# CHGslaBAT.net
KiCad netlist of a schematic drawn in EAGLE
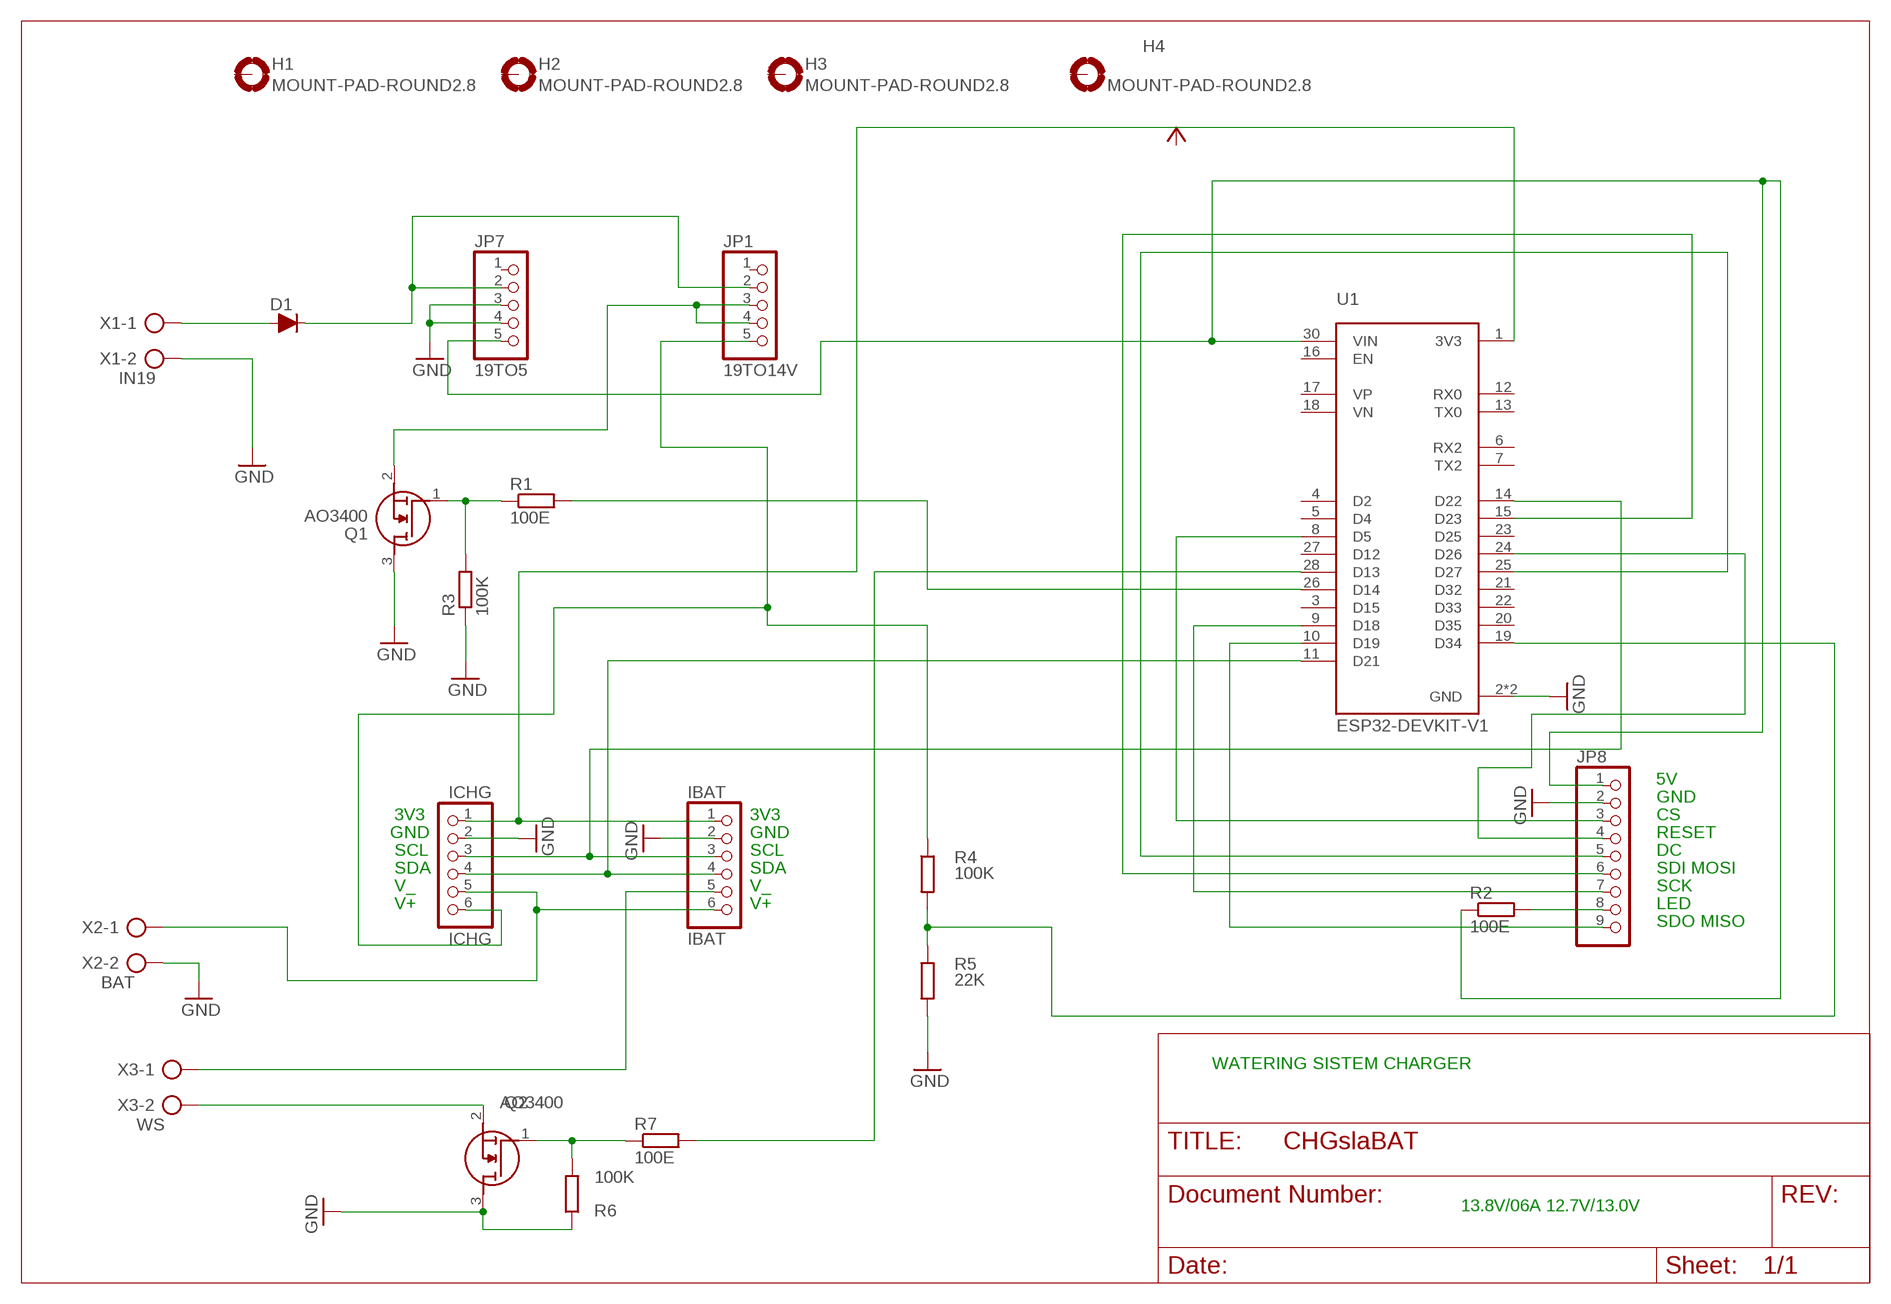
[diagram p0: schematic, sheet 1]

(export (version "E")
  (design (tool "Eeschema 10.0.6"))
  (components
    (comp (ref "D1")
      (value "D-FILL-SOD-80")
      (footprint "eagle-import:SOD80")
      (libsource (lib "eagle-import") (part "D-FILL-SOD-80"))
    )
    (comp (ref "H1")
      (value "MOUNT-PAD-ROUND2.8")
      (footprint "eagle-import:2,8-PAD")
      (libsource (lib "eagle-import") (part "MOUNT-PAD-ROUND2.8"))
    )
    (comp (ref "H2")
      (value "MOUNT-PAD-ROUND2.8")
      (footprint "eagle-import:2,8-PAD")
      (libsource (lib "eagle-import") (part "MOUNT-PAD-ROUND2.8"))
    )
    (comp (ref "H3")
      (value "MOUNT-PAD-ROUND2.8")
      (footprint "eagle-import:2,8-PAD")
      (libsource (lib "eagle-import") (part "MOUNT-PAD-ROUND2.8"))
    )
    (comp (ref "H4")
      (value "MOUNT-PAD-ROUND2.8")
      (footprint "eagle-import:2,8-PAD")
      (libsource (lib "eagle-import") (part "MOUNT-PAD-ROUND2.8"))
    )
    (comp (ref "IBAT")
      (value "IBAT")
      (footprint "eagle-import:1X06")
      (libsource (lib "eagle-import") (part "PINHD-1X6"))
    )
    (comp (ref "ICHG")
      (value "ICHG")
      (footprint "eagle-import:1X06")
      (libsource (lib "eagle-import") (part "PINHD-1X6"))
    )
    (comp (ref "JP1")
      (value "19TO14V")
      (footprint "eagle-import:1X05")
      (libsource (lib "eagle-import") (part "PINHD-1X5"))
    )
    (comp (ref "JP7")
      (value "19TO5")
      (footprint "eagle-import:1X05")
      (libsource (lib "eagle-import") (part "PINHD-1X5"))
    )
    (comp (ref "JP8")
      (value "PINHD-1X9")
      (footprint "eagle-import:1X09")
      (libsource (lib "eagle-import") (part "PINHD-1X9"))
    )
    (comp (ref "Q1")
      (value "AO3400")
      (footprint "eagle-import:SOT95P280X125-3N")
      (fields (field (name "MF") "Microdiode Electronics"))
      (libsource (lib "eagle-import") (part "AO3400"))
    )
    (comp (ref "Q2")
      (value "AO3400")
      (footprint "eagle-import:SOT95P280X125-3N")
      (description "Trans MOSFET N-CH 30V 5.7A 3-Pin SOT-23 T/R")
      (fields
        (field (name "MF") "Microdiode Electronics")
        (field (name "AVAILABILITY") "Not in stock")
        (field (name "CHECK_PRICES") "https://www.snapeda.com/parts/AO3400/Applied+Avionics/view-part/?ref=eda")
        (field (name "MF_1") "Microdiode Electronics")
        (field (name "MP") "AO3400")
        (field (name "PACKAGE") "None")
        (field (name "PRICE") "None")
        (field (name "SNAPEDA_LINK") "https://www.snapeda.com/parts/AO3400/Applied+Avionics/view-part/?ref=snap")
      )
      (libsource (lib "eagle-import") (part "AO3400"))
    )
    (comp (ref "R1")
      (value "100E")
      (footprint "eagle-import:M0805")
      (libsource (lib "eagle-import") (part "R-EU_M0805"))
    )
    (comp (ref "R2")
      (value "100E")
      (footprint "eagle-import:M0805")
      (libsource (lib "eagle-import") (part "R-EU_M0805"))
    )
    (comp (ref "R3")
      (value "100K")
      (footprint "eagle-import:M0805")
      (libsource (lib "eagle-import") (part "R-EU_M0805"))
    )
    (comp (ref "R4")
      (value "100K")
      (footprint "eagle-import:M0805")
      (libsource (lib "eagle-import") (part "R-EU_M0805"))
    )
    (comp (ref "R5")
      (value "22K")
      (footprint "eagle-import:M0805")
      (libsource (lib "eagle-import") (part "R-EU_M0805"))
    )
    (comp (ref "R6")
      (value "100K")
      (footprint "eagle-import:M0805")
      (libsource (lib "eagle-import") (part "R-EU_M0805"))
    )
    (comp (ref "R7")
      (value "100E")
      (footprint "eagle-import:M0805")
      (libsource (lib "eagle-import") (part "R-EU_M0805"))
    )
    (comp (ref "U1")
      (value "ESP32-DEVKIT-V1")
      (footprint "eagle-import:MODULE_ESP32_DEVKIT_V1")
      (fields (field (name "MF") "Do it"))
      (libsource (lib "eagle-import") (part "ESP32-DEVKIT-V1"))
    )
    (comp (ref "X1")
      (value "IN19")
      (footprint "eagle-import:AK300_2")
      (libsource (lib "eagle-import") (part "AK300/2"))
    )
    (comp (ref "X2")
      (value "BAT")
      (footprint "eagle-import:AK300_2")
      (libsource (lib "eagle-import") (part "AK300/2"))
    )
    (comp (ref "X3")
      (value "WS")
      (footprint "eagle-import:AK300_2")
      (libsource (lib "eagle-import") (part "AK300/2"))
    )
  )
  (nets
    (net (code "2") (name "GND") (class "Default")
      (node (ref "IBAT") (pin "2") (pinfunction "2_2") (pintype "passive"))
      (node (ref "ICHG") (pin "2") (pinfunction "2_2") (pintype "passive"))
      (node (ref "JP7") (pin "3") (pinfunction "3_3") (pintype "passive"))
      (node (ref "JP7") (pin "4") (pinfunction "4_4") (pintype "passive"))
      (node (ref "JP8") (pin "2") (pinfunction "2_2") (pintype "passive"))
      (node (ref "Q1") (pin "3") (pinfunction "D_3") (pintype "bidirectional"))
      (node (ref "Q2") (pin "3") (pinfunction "D_3") (pintype "bidirectional"))
      (node (ref "R3") (pin "1") (pinfunction "1_1") (pintype "passive"))
      (node (ref "R5") (pin "2") (pinfunction "2_2") (pintype "passive"))
      (node (ref "R6") (pin "1") (pinfunction "1_1") (pintype "passive"))
      (node (ref "U1") (pin "2") (pinfunction "GND_2") (pintype "power_in"))
      (node (ref "U1") (pin "29") (pinfunction "GND_29") (pintype "power_in"))
      (node (ref "X1") (pin "2") (pinfunction "KL_2") (pintype "passive"))
      (node (ref "X2") (pin "2") (pinfunction "KL_2") (pintype "passive"))
    )
    (net (code "3") (name "Net-(D1-A)") (class "Default")
      (node (ref "D1") (pin "2") (pinfunction "A_2") (pintype "passive"))
      (node (ref "X1") (pin "1") (pinfunction "KL_1") (pintype "passive"))
    )
    (net (code "4") (name "Net-(D1-C)") (class "Default")
      (node (ref "D1") (pin "1") (pinfunction "C_1") (pintype "passive"))
      (node (ref "JP1") (pin "2") (pinfunction "2_2") (pintype "passive"))
      (node (ref "JP7") (pin "2") (pinfunction "2_2") (pintype "passive"))
    )
    (net (code "5") (name "Net-(ICHG-Pad6)") (class "Default")
      (node (ref "ICHG") (pin "6") (pinfunction "6_6") (pintype "passive"))
      (node (ref "JP1") (pin "5") (pinfunction "5_5") (pintype "passive"))
      (node (ref "R4") (pin "1") (pinfunction "1_1") (pintype "passive"))
    )
    (net (code "6") (name "Net-(JP8-Pad8)") (class "Default")
      (node (ref "JP8") (pin "8") (pinfunction "8_8") (pintype "passive"))
      (node (ref "R2") (pin "2") (pinfunction "2_2") (pintype "passive"))
    )
    (net (code "7") (name "Net-(Q1-G)") (class "Default")
      (node (ref "Q1") (pin "1") (pinfunction "G_1") (pintype "bidirectional"))
      (node (ref "R1") (pin "1") (pinfunction "1_1") (pintype "passive"))
      (node (ref "R3") (pin "2") (pinfunction "2_2") (pintype "passive"))
    )
    (net (code "8") (name "Net-(Q1-S)") (class "Default")
      (node (ref "JP1") (pin "3") (pinfunction "3_3") (pintype "passive"))
      (node (ref "JP1") (pin "4") (pinfunction "4_4") (pintype "passive"))
      (node (ref "Q1") (pin "2") (pinfunction "S_2") (pintype "bidirectional"))
    )
    (net (code "9") (name "Net-(Q2-G)") (class "Default")
      (node (ref "Q2") (pin "1") (pinfunction "G_1") (pintype "bidirectional"))
      (node (ref "R6") (pin "2") (pinfunction "2_2") (pintype "passive"))
      (node (ref "R7") (pin "1") (pinfunction "1_1") (pintype "passive"))
    )
    (net (code "10") (name "Net-(Q2-S)") (class "Default")
      (node (ref "Q2") (pin "2") (pinfunction "S_2") (pintype "bidirectional"))
      (node (ref "X3") (pin "2") (pinfunction "KL_2") (pintype "passive"))
    )
    (net (code "11") (name "Net-(U1-3V3)") (class "Default")
      (node (ref "IBAT") (pin "1") (pinfunction "1_1") (pintype "passive"))
      (node (ref "ICHG") (pin "1") (pinfunction "1_1") (pintype "passive"))
      (node (ref "U1") (pin "1") (pinfunction "3V3_1") (pintype "output"))
    )
    (net (code "12") (name "Net-(U1-D5)") (class "Default")
      (node (ref "JP8") (pin "3") (pinfunction "3_3") (pintype "passive"))
      (node (ref "U1") (pin "8") (pinfunction "D5_8") (pintype "bidirectional"))
    )
    (net (code "13") (name "Net-(U1-D13)") (class "Default")
      (node (ref "R7") (pin "2") (pinfunction "2_2") (pintype "passive"))
      (node (ref "U1") (pin "28") (pinfunction "D13_28") (pintype "bidirectional"))
    )
    (net (code "14") (name "Net-(U1-D14)") (class "Default")
      (node (ref "R1") (pin "2") (pinfunction "2_2") (pintype "passive"))
      (node (ref "U1") (pin "26") (pinfunction "D14_26") (pintype "bidirectional"))
    )
    (net (code "15") (name "Net-(U1-D18)") (class "Default")
      (node (ref "JP8") (pin "7") (pinfunction "7_7") (pintype "passive"))
      (node (ref "U1") (pin "9") (pinfunction "D18_9") (pintype "bidirectional"))
    )
    (net (code "16") (name "Net-(U1-D19)") (class "Default")
      (node (ref "JP8") (pin "9") (pinfunction "9_9") (pintype "passive"))
      (node (ref "U1") (pin "10") (pinfunction "D19_10") (pintype "bidirectional"))
    )
    (net (code "17") (name "Net-(U1-D21)") (class "Default")
      (node (ref "IBAT") (pin "4") (pinfunction "4_4") (pintype "passive"))
      (node (ref "ICHG") (pin "4") (pinfunction "4_4") (pintype "passive"))
      (node (ref "U1") (pin "11") (pinfunction "D21_11") (pintype "bidirectional"))
    )
    (net (code "18") (name "Net-(U1-D22)") (class "Default")
      (node (ref "IBAT") (pin "3") (pinfunction "3_3") (pintype "passive"))
      (node (ref "ICHG") (pin "3") (pinfunction "3_3") (pintype "passive"))
      (node (ref "U1") (pin "14") (pinfunction "D22_14") (pintype "bidirectional"))
    )
    (net (code "19") (name "Net-(U1-D23)") (class "Default")
      (node (ref "JP8") (pin "6") (pinfunction "6_6") (pintype "passive"))
      (node (ref "U1") (pin "15") (pinfunction "D23_15") (pintype "bidirectional"))
    )
    (net (code "20") (name "Net-(U1-D26)") (class "Default")
      (node (ref "JP8") (pin "4") (pinfunction "4_4") (pintype "passive"))
      (node (ref "U1") (pin "24") (pinfunction "D26_24") (pintype "bidirectional"))
    )
    (net (code "21") (name "Net-(U1-D27)") (class "Default")
      (node (ref "JP8") (pin "5") (pinfunction "5_5") (pintype "passive"))
      (node (ref "U1") (pin "25") (pinfunction "D27_25") (pintype "bidirectional"))
    )
    (net (code "22") (name "Net-(U1-D34)") (class "Default")
      (node (ref "R4") (pin "2") (pinfunction "2_2") (pintype "passive"))
      (node (ref "R5") (pin "1") (pinfunction "1_1") (pintype "passive"))
      (node (ref "U1") (pin "19") (pinfunction "D34_19") (pintype "bidirectional"))
    )
    (net (code "23") (name "Net-(U1-VIN)") (class "Default")
      (node (ref "JP7") (pin "5") (pinfunction "5_5") (pintype "passive"))
      (node (ref "JP8") (pin "1") (pinfunction "1_1") (pintype "passive"))
      (node (ref "R2") (pin "1") (pinfunction "1_1") (pintype "passive"))
      (node (ref "U1") (pin "30") (pinfunction "VIN_30") (pintype "input"))
    )
    (net (code "24") (name "Net-(X2A-KL)") (class "Default")
      (node (ref "IBAT") (pin "6") (pinfunction "6_6") (pintype "passive"))
      (node (ref "ICHG") (pin "5") (pinfunction "5_5") (pintype "passive"))
      (node (ref "X2") (pin "1") (pinfunction "KL_1") (pintype "passive"))
    )
    (net (code "25") (name "Net-(X3A-KL)") (class "Default")
      (node (ref "IBAT") (pin "5") (pinfunction "5_5") (pintype "passive"))
      (node (ref "X3") (pin "1") (pinfunction "KL_1") (pintype "passive"))
    )
    (net (code "26") (name "unconnected-(H1-MOUNT-PadB2,8)") (class "Default")
      (node (ref "H1") (pin "B2,8") (pinfunction "MOUNT_B2,8") (pintype "passive"))
    )
    (net (code "27") (name "unconnected-(H2-MOUNT-PadB2,8)") (class "Default")
      (node (ref "H2") (pin "B2,8") (pinfunction "MOUNT_B2,8") (pintype "passive"))
    )
    (net (code "28") (name "unconnected-(H3-MOUNT-PadB2,8)") (class "Default")
      (node (ref "H3") (pin "B2,8") (pinfunction "MOUNT_B2,8") (pintype "passive"))
    )
    (net (code "29") (name "unconnected-(H4-MOUNT-PadB2,8)") (class "Default")
      (node (ref "H4") (pin "B2,8") (pinfunction "MOUNT_B2,8") (pintype "passive"))
    )
    (net (code "30") (name "unconnected-(JP1-Pad1)") (class "Default")
      (node (ref "JP1") (pin "1") (pinfunction "1_1") (pintype "passive"))
    )
    (net (code "31") (name "unconnected-(JP7-Pad1)") (class "Default")
      (node (ref "JP7") (pin "1") (pinfunction "1_1") (pintype "passive"))
    )
    (net (code "32") (name "unconnected-(U1-D2-Pad4)") (class "Default")
      (node (ref "U1") (pin "4") (pinfunction "D2_4") (pintype "bidirectional"))
    )
    (net (code "33") (name "unconnected-(U1-D4-Pad5)") (class "Default")
      (node (ref "U1") (pin "5") (pinfunction "D4_5") (pintype "bidirectional"))
    )
    (net (code "34") (name "unconnected-(U1-D12-Pad27)") (class "Default")
      (node (ref "U1") (pin "27") (pinfunction "D12_27") (pintype "bidirectional"))
    )
    (net (code "35") (name "unconnected-(U1-D15-Pad3)") (class "Default")
      (node (ref "U1") (pin "3") (pinfunction "D15_3") (pintype "bidirectional"))
    )
    (net (code "36") (name "unconnected-(U1-D25-Pad23)") (class "Default")
      (node (ref "U1") (pin "23") (pinfunction "D25_23") (pintype "bidirectional"))
    )
    (net (code "37") (name "unconnected-(U1-D32-Pad21)") (class "Default")
      (node (ref "U1") (pin "21") (pinfunction "D32_21") (pintype "bidirectional"))
    )
    (net (code "38") (name "unconnected-(U1-D33-Pad22)") (class "Default")
      (node (ref "U1") (pin "22") (pinfunction "D33_22") (pintype "bidirectional"))
    )
    (net (code "39") (name "unconnected-(U1-D35-Pad20)") (class "Default")
      (node (ref "U1") (pin "20") (pinfunction "D35_20") (pintype "bidirectional"))
    )
    (net (code "40") (name "unconnected-(U1-EN-Pad16)") (class "Default")
      (node (ref "U1") (pin "16") (pinfunction "EN_16") (pintype "input"))
    )
    (net (code "41") (name "unconnected-(U1-RX0-Pad12)") (class "Default")
      (node (ref "U1") (pin "12") (pinfunction "RX0_12") (pintype "input"))
    )
    (net (code "42") (name "unconnected-(U1-RX2-Pad6)") (class "Default")
      (node (ref "U1") (pin "6") (pinfunction "RX2_6") (pintype "input"))
    )
    (net (code "43") (name "unconnected-(U1-TX0-Pad13)") (class "Default")
      (node (ref "U1") (pin "13") (pinfunction "TX0_13") (pintype "output"))
    )
    (net (code "44") (name "unconnected-(U1-TX2-Pad7)") (class "Default")
      (node (ref "U1") (pin "7") (pinfunction "TX2_7") (pintype "output"))
    )
    (net (code "45") (name "unconnected-(U1-VN-Pad18)") (class "Default")
      (node (ref "U1") (pin "18") (pinfunction "VN_18") (pintype "bidirectional"))
    )
    (net (code "46") (name "unconnected-(U1-VP-Pad17)") (class "Default")
      (node (ref "U1") (pin "17") (pinfunction "VP_17") (pintype "bidirectional"))
    )
  )
)
